# jetson_ros_button.net
KiCad netlist of a schematic drawn in EAGLE
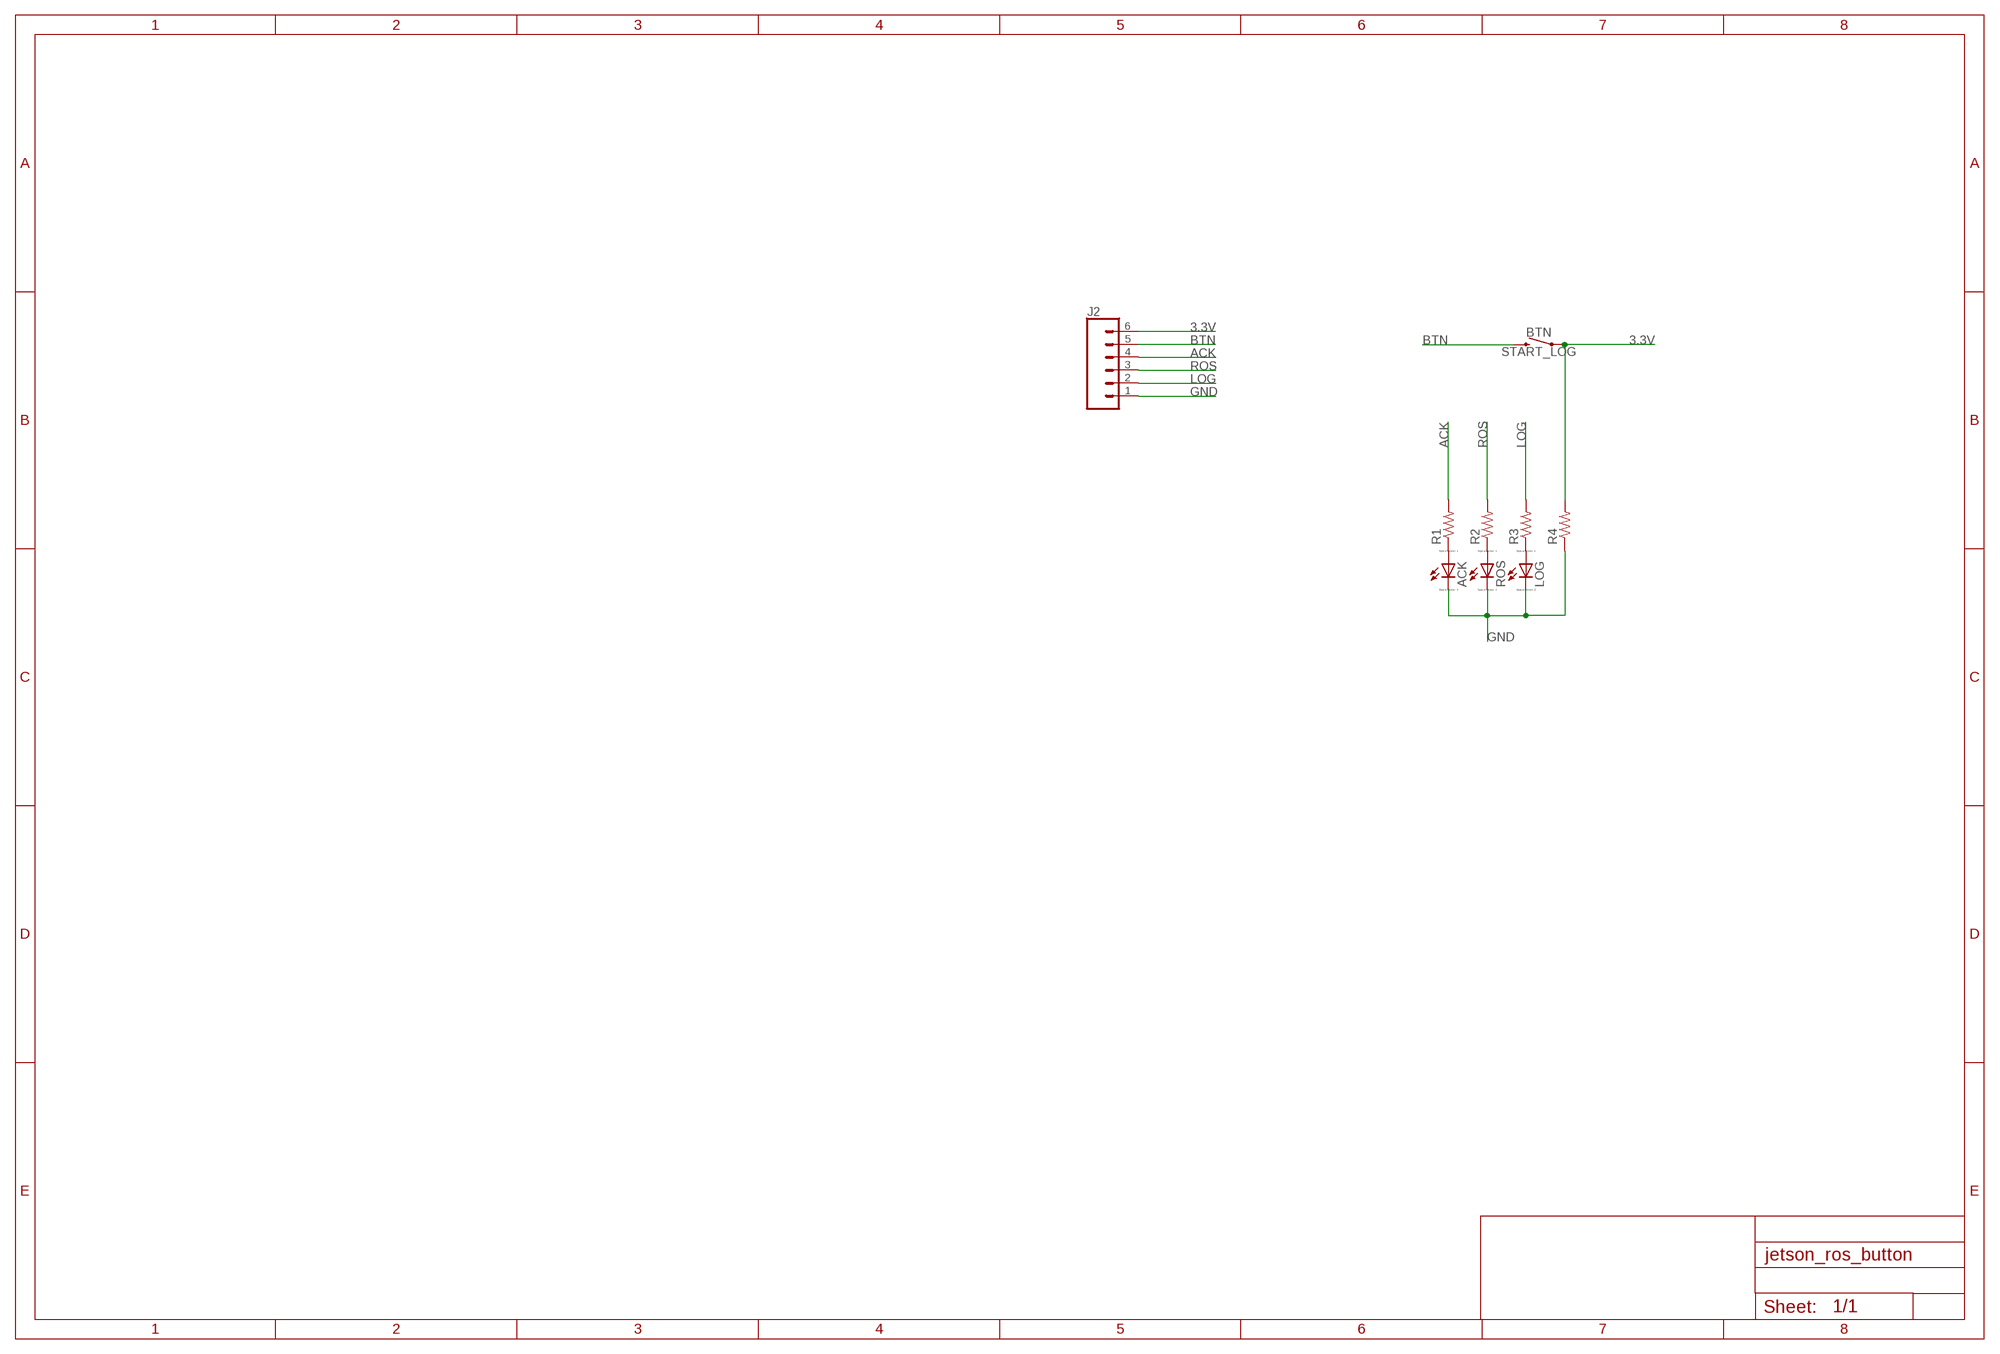
[diagram p0: schematic, sheet 1]

(export (version "E")
  (design (tool "Eeschema 10.0.6"))
  (components
    (comp (ref "ACK")
      (value "LED_E")
      (footprint "eagle-import:LED_1206")
      (libsource (lib "eagle-import") (part "LED_E"))
    )
    (comp (ref "BTN")
      (value "START_LOG")
      (footprint "eagle-import:TACTILE_SWITCH_PTH_6.0MM")
      (libsource (lib "eagle-import") (part "MOMENTARY-SWITCH-SPST-PTH-6.0MM"))
    )
    (comp (ref "J2")
      (value "CONN_06SILK_FEMALE_PTH")
      (footprint "eagle-import:1X06")
      (libsource (lib "eagle-import") (part "CONN_06SILK_FEMALE_PTH"))
    )
    (comp (ref "LOG")
      (value "LED_E")
      (footprint "eagle-import:LED_1206")
      (libsource (lib "eagle-import") (part "LED_E"))
    )
    (comp (ref "R1")
      (value "R-US_0204/7")
      (footprint "eagle-import:0204_7")
      (libsource (lib "eagle-import") (part "R-US_0204/7"))
    )
    (comp (ref "R2")
      (value "R-US_0204/7")
      (footprint "eagle-import:0204_7")
      (libsource (lib "eagle-import") (part "R-US_0204/7"))
    )
    (comp (ref "R3")
      (value "R-US_0204/7")
      (footprint "eagle-import:0204_7")
      (libsource (lib "eagle-import") (part "R-US_0204/7"))
    )
    (comp (ref "R4")
      (value "R-US_0204/7")
      (footprint "eagle-import:0204_7")
      (libsource (lib "eagle-import") (part "R-US_0204/7"))
    )
    (comp (ref "ROS")
      (value "LED_E")
      (footprint "eagle-import:LED_1206")
      (libsource (lib "eagle-import") (part "LED_E"))
    )
  )
  (nets
    (net (code "1") (name "/3.3V") (class "Default")
      (node (ref "BTN") (pin "1") (pinfunction "1_1") (pintype "passive"))
      (node (ref "J2") (pin "6") (pinfunction "6_6") (pintype "passive"))
      (node (ref "R4") (pin "2") (pinfunction "2_2") (pintype "passive"))
    )
    (net (code "2") (name "/ACK") (class "Default")
      (node (ref "J2") (pin "4") (pinfunction "4_4") (pintype "passive"))
      (node (ref "R1") (pin "2") (pinfunction "2_2") (pintype "passive"))
    )
    (net (code "3") (name "/BTN") (class "Default")
      (node (ref "BTN") (pin "3") (pinfunction "2_3") (pintype "passive"))
      (node (ref "J2") (pin "5") (pinfunction "5_5") (pintype "passive"))
    )
    (net (code "4") (name "/GND") (class "Default")
      (node (ref "ACK") (pin "C") (pinfunction "C_C") (pintype "passive"))
      (node (ref "J2") (pin "1") (pinfunction "1_1") (pintype "passive"))
      (node (ref "LOG") (pin "C") (pinfunction "C_C") (pintype "passive"))
      (node (ref "R4") (pin "1") (pinfunction "1_1") (pintype "passive"))
      (node (ref "ROS") (pin "C") (pinfunction "C_C") (pintype "passive"))
    )
    (net (code "5") (name "/LOG") (class "Default")
      (node (ref "J2") (pin "2") (pinfunction "2_2") (pintype "passive"))
      (node (ref "R3") (pin "2") (pinfunction "2_2") (pintype "passive"))
    )
    (net (code "6") (name "/ROS") (class "Default")
      (node (ref "J2") (pin "3") (pinfunction "3_3") (pintype "passive"))
      (node (ref "R2") (pin "2") (pinfunction "2_2") (pintype "passive"))
    )
    (net (code "7") (name "Net-(ACK-PadA)") (class "Default")
      (node (ref "ACK") (pin "A") (pinfunction "A_A") (pintype "passive"))
      (node (ref "R1") (pin "1") (pinfunction "1_1") (pintype "passive"))
    )
    (net (code "8") (name "Net-(LOG-PadA)") (class "Default")
      (node (ref "LOG") (pin "A") (pinfunction "A_A") (pintype "passive"))
      (node (ref "R3") (pin "1") (pinfunction "1_1") (pintype "passive"))
    )
    (net (code "9") (name "Net-(R2-Pad1)") (class "Default")
      (node (ref "R2") (pin "1") (pinfunction "1_1") (pintype "passive"))
      (node (ref "ROS") (pin "A") (pinfunction "A_A") (pintype "passive"))
    )
  )
)
